# 1_P1.net
KiCad netlist of a schematic drawn in Altium Designer
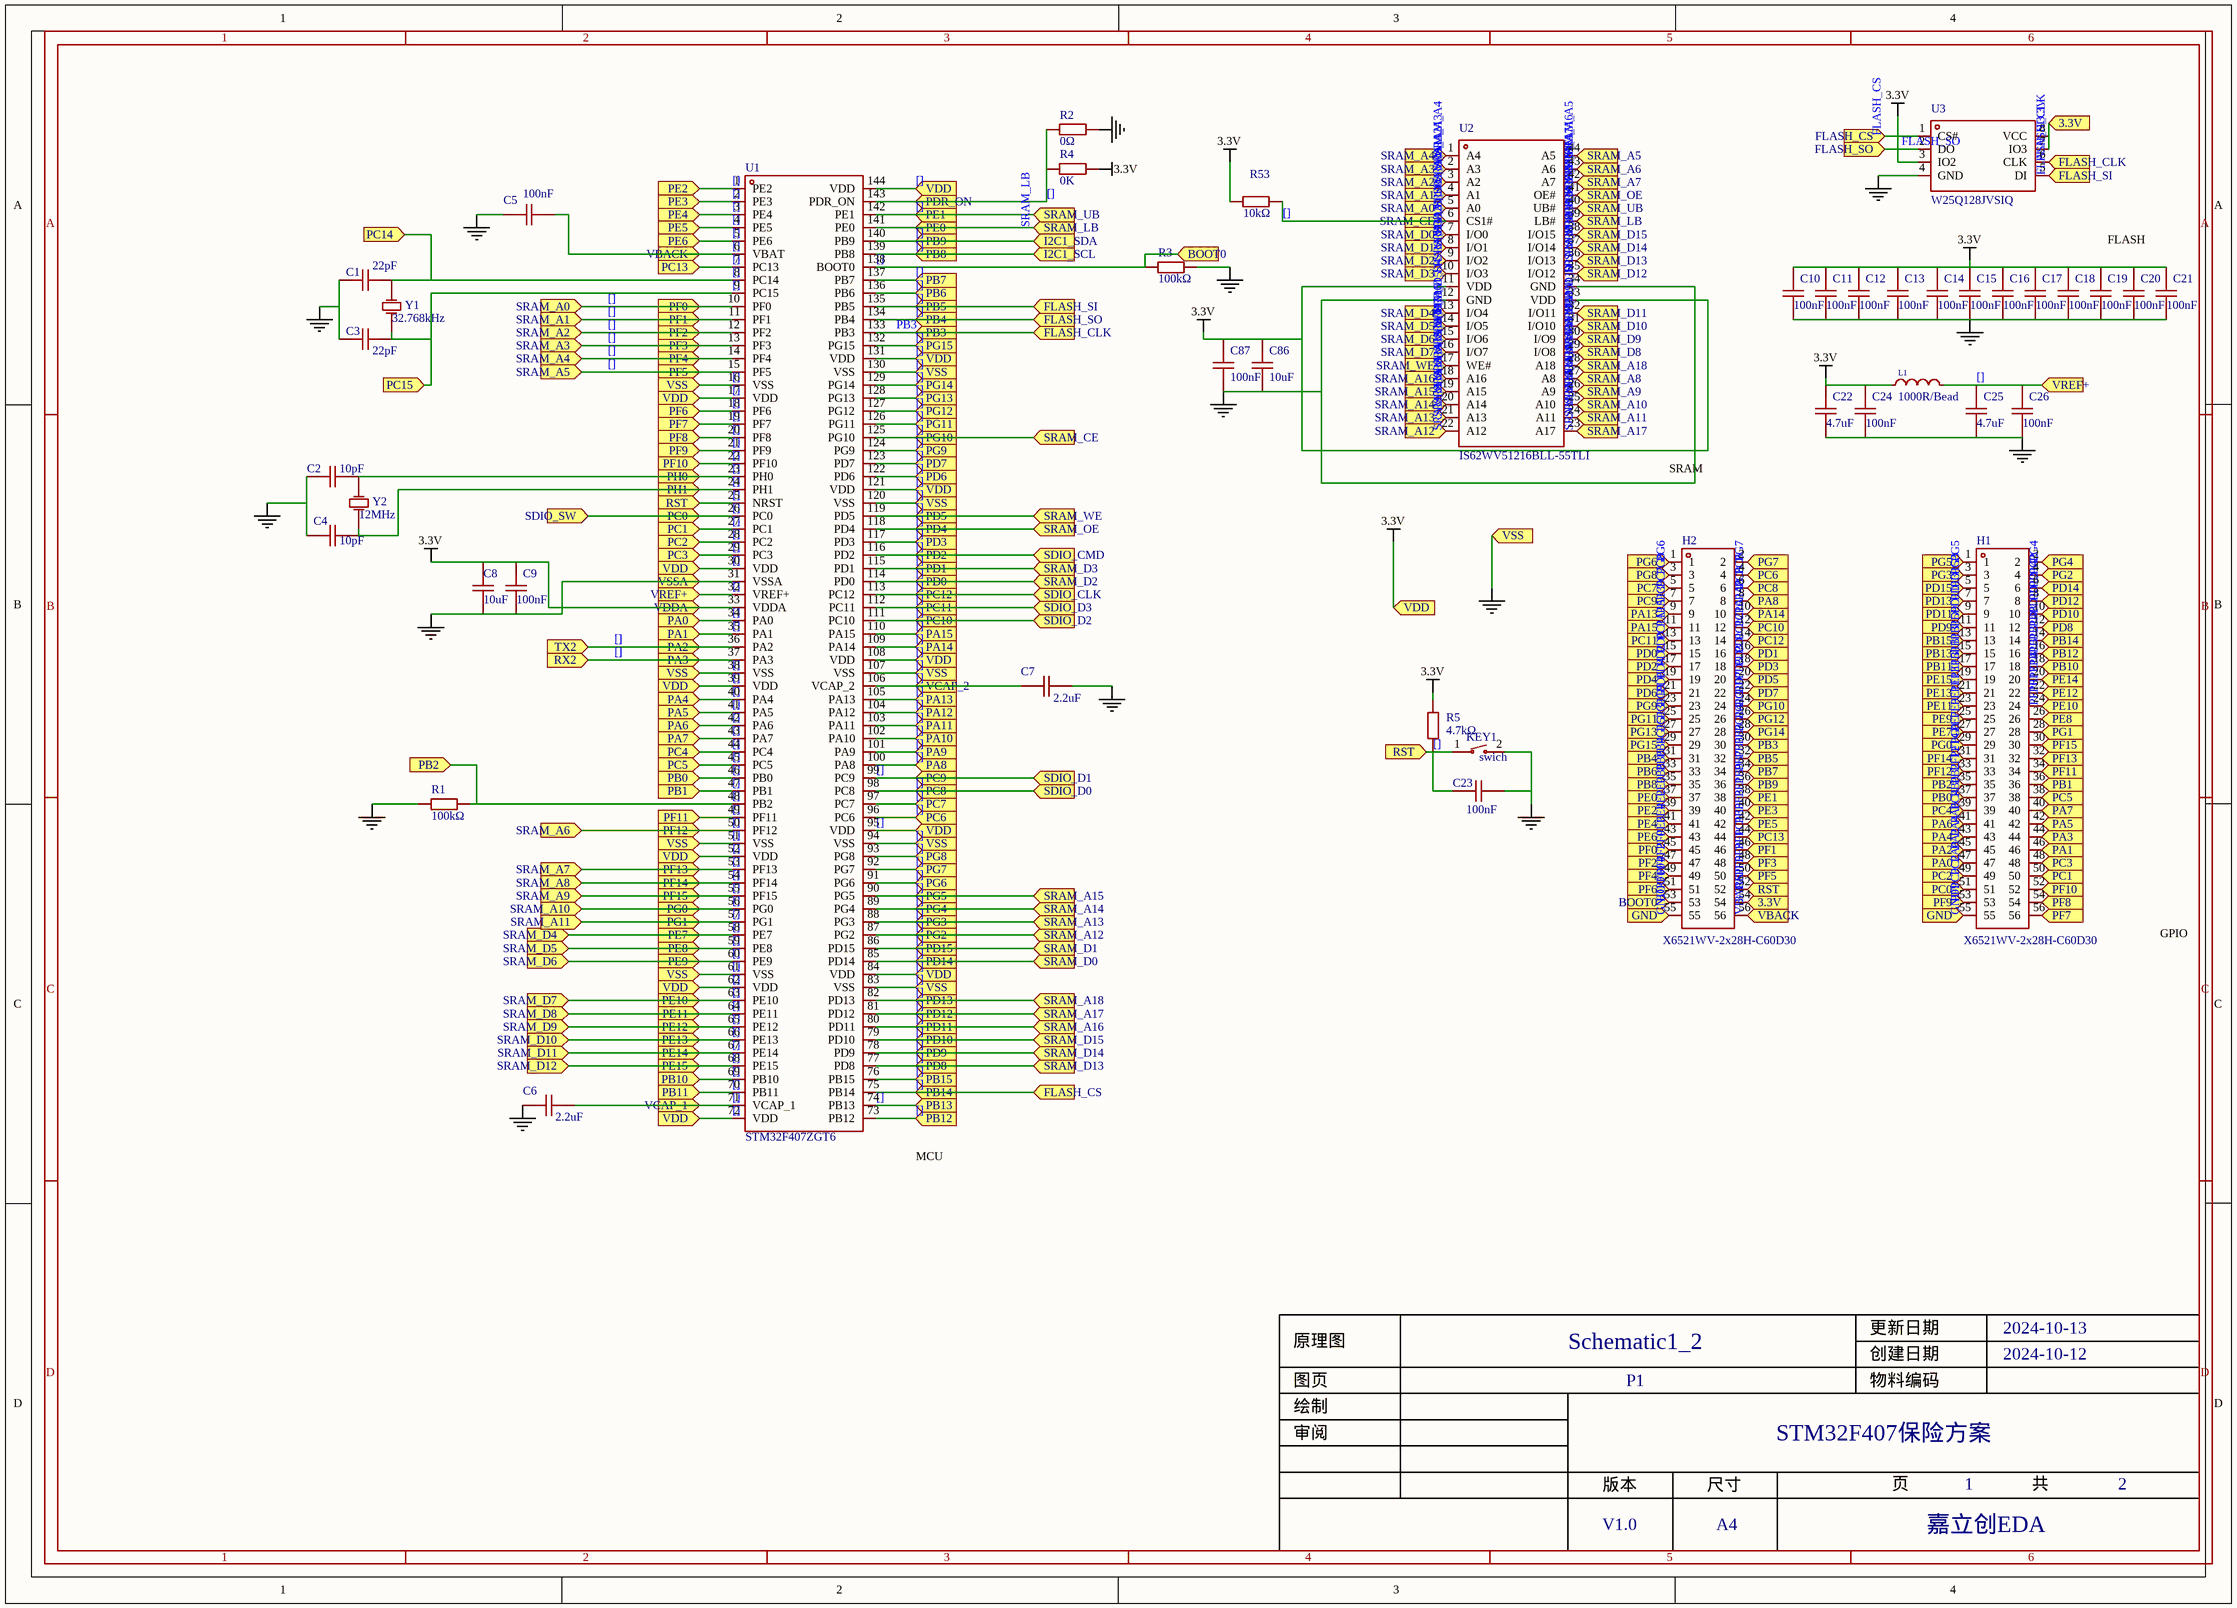
[diagram p0: 1_P1.schdoc]

(export (version "E")
  (design (tool "Eeschema 10.0.6"))
  (components
    (comp (ref "C1")
      (value "22pF")
      (footprint "C0805")
      (description "容值:22pF;精度:±5%;额定电压:50V;材质(温度系数):NP0;")
      (fields
        (field (name "MANUFACTURER") "YAGEO(国巨)")
        (field (name "MANUFACTURER PART") "CC0805JRNPO9BN220")
      )
      (libsource (lib "altium-import") (part "root_0_CC0805JRNPO9BN220_"))
    )
    (comp (ref "C2")
      (value "10pF")
      (footprint "C0805")
      (description "容值:10pF;精度:±5%;额定电压:50V;材质(温度系数):NP0;")
      (fields
        (field (name "MANUFACTURER") "YAGEO(国巨)")
        (field (name "MANUFACTURER PART") "CC0805JRNPO9BN100")
      )
      (libsource (lib "altium-import") (part "root_0_CC0805JRNPO9BN100_"))
    )
    (comp (ref "C3")
      (value "22pF")
      (footprint "C0805")
      (description "容值:22pF;精度:±5%;额定电压:50V;材质(温度系数):NP0;")
      (fields
        (field (name "MANUFACTURER") "YAGEO(国巨)")
        (field (name "MANUFACTURER PART") "CC0805JRNPO9BN220")
      )
      (libsource (lib "altium-import") (part "root_0_CC0805JRNPO9BN220_"))
    )
    (comp (ref "C4")
      (value "10pF")
      (footprint "C0805")
      (description "容值:10pF;精度:±5%;额定电压:50V;材质(温度系数):NP0;")
      (fields
        (field (name "MANUFACTURER") "YAGEO(国巨)")
        (field (name "MANUFACTURER PART") "CC0805JRNPO9BN100")
      )
      (libsource (lib "altium-import") (part "root_0_CC0805JRNPO9BN100_"))
    )
    (comp (ref "C5")
      (value "100nF")
      (footprint "C0805")
      (description "容值:100nF;精度:±10%;额定电压:50V;材质(温度系数):X7R;")
      (fields
        (field (name "MANUFACTURER") "YAGEO(国巨)")
        (field (name "MANUFACTURER PART") "CC0805KRX7R9BB104")
      )
      (libsource (lib "altium-import") (part "root_2_CC0805KRX7R9BB104_"))
    )
    (comp (ref "C6")
      (value "2.2uF")
      (footprint "C0805")
      (description "容值:2.2uF;精度:±10%;额定电压:50V;材质(温度系数):X7R;")
      (fields
        (field (name "MANUFACTURER") "YAGEO(国巨)")
        (field (name "MANUFACTURER PART") "CC0805KKX7R9BB225")
      )
      (libsource (lib "altium-import") (part "root_2_CC0805KKX7R9BB225_"))
    )
    (comp (ref "C7")
      (value "2.2uF")
      (footprint "C0805")
      (description "容值:2.2uF;精度:±10%;额定电压:50V;材质(温度系数):X7R;")
      (fields
        (field (name "MANUFACTURER") "YAGEO(国巨)")
        (field (name "MANUFACTURER PART") "CC0805KKX7R9BB225")
      )
      (libsource (lib "altium-import") (part "root_2_CC0805KKX7R9BB225_"))
    )
    (comp (ref "C8")
      (value "10uF")
      (footprint "C0805")
      (description "容值:10uF;精度:±10%;额定电压:25V;材质(温度系数):X5R;")
      (fields
        (field (name "MANUFACTURER") "YAGEO(国巨)")
        (field (name "MANUFACTURER PART") "CC0805KKX5R8BB106")
      )
      (libsource (lib "altium-import") (part "root_3_CC0805KKX5R8BB106_C89831_"))
    )
    (comp (ref "C9")
      (value "100nF")
      (footprint "C0805")
      (description "容值:100nF;精度:±10%;额定电压:50V;材质(温度系数):X7R;")
      (fields
        (field (name "MANUFACTURER") "YAGEO(国巨)")
        (field (name "MANUFACTURER PART") "CC0805KRX7R9BB104")
      )
      (libsource (lib "altium-import") (part "root_3_CC0805KRX7R9BB104_"))
    )
    (comp (ref "C10")
      (value "100nF")
      (footprint "C0805")
      (description "容值:100nF;精度:±10%;额定电压:50V;材质(温度系数):X7R;")
      (fields
        (field (name "MANUFACTURER") "YAGEO(国巨)")
        (field (name "MANUFACTURER PART") "CC0805KRX7R9BB104")
      )
      (libsource (lib "altium-import") (part "root_1_CC0805KRX7R9BB104_"))
    )
    (comp (ref "C11")
      (value "100nF")
      (footprint "C0805")
      (description "容值:100nF;精度:±10%;额定电压:50V;材质(温度系数):X7R;")
      (fields
        (field (name "MANUFACTURER") "YAGEO(国巨)")
        (field (name "MANUFACTURER PART") "CC0805KRX7R9BB104")
      )
      (libsource (lib "altium-import") (part "root_1_CC0805KRX7R9BB104_"))
    )
    (comp (ref "C12")
      (value "100nF")
      (footprint "C0805")
      (description "容值:100nF;精度:±10%;额定电压:50V;材质(温度系数):X7R;")
      (fields
        (field (name "MANUFACTURER") "YAGEO(国巨)")
        (field (name "MANUFACTURER PART") "CC0805KRX7R9BB104")
      )
      (libsource (lib "altium-import") (part "root_1_CC0805KRX7R9BB104_"))
    )
    (comp (ref "C13")
      (value "100nF")
      (footprint "C0805")
      (description "容值:100nF;精度:±10%;额定电压:50V;材质(温度系数):X7R;")
      (fields
        (field (name "MANUFACTURER") "YAGEO(国巨)")
        (field (name "MANUFACTURER PART") "CC0805KRX7R9BB104")
      )
      (libsource (lib "altium-import") (part "root_1_CC0805KRX7R9BB104_"))
    )
    (comp (ref "C14")
      (value "100nF")
      (footprint "C0805")
      (description "容值:100nF;精度:±10%;额定电压:50V;材质(温度系数):X7R;")
      (fields
        (field (name "MANUFACTURER") "YAGEO(国巨)")
        (field (name "MANUFACTURER PART") "CC0805KRX7R9BB104")
      )
      (libsource (lib "altium-import") (part "root_1_CC0805KRX7R9BB104_"))
    )
    (comp (ref "C15")
      (value "100nF")
      (footprint "C0805")
      (description "容值:100nF;精度:±10%;额定电压:50V;材质(温度系数):X7R;")
      (fields
        (field (name "MANUFACTURER") "YAGEO(国巨)")
        (field (name "MANUFACTURER PART") "CC0805KRX7R9BB104")
      )
      (libsource (lib "altium-import") (part "root_1_CC0805KRX7R9BB104_"))
    )
    (comp (ref "C16")
      (value "100nF")
      (footprint "C0805")
      (description "容值:100nF;精度:±10%;额定电压:50V;材质(温度系数):X7R;")
      (fields
        (field (name "MANUFACTURER") "YAGEO(国巨)")
        (field (name "MANUFACTURER PART") "CC0805KRX7R9BB104")
      )
      (libsource (lib "altium-import") (part "root_1_CC0805KRX7R9BB104_"))
    )
    (comp (ref "C17")
      (value "100nF")
      (footprint "C0805")
      (description "容值:100nF;精度:±10%;额定电压:50V;材质(温度系数):X7R;")
      (fields
        (field (name "MANUFACTURER") "YAGEO(国巨)")
        (field (name "MANUFACTURER PART") "CC0805KRX7R9BB104")
      )
      (libsource (lib "altium-import") (part "root_1_CC0805KRX7R9BB104_"))
    )
    (comp (ref "C18")
      (value "100nF")
      (footprint "C0805")
      (description "容值:100nF;精度:±10%;额定电压:50V;材质(温度系数):X7R;")
      (fields
        (field (name "MANUFACTURER") "YAGEO(国巨)")
        (field (name "MANUFACTURER PART") "CC0805KRX7R9BB104")
      )
      (libsource (lib "altium-import") (part "root_1_CC0805KRX7R9BB104_"))
    )
    (comp (ref "C19")
      (value "100nF")
      (footprint "C0805")
      (description "容值:100nF;精度:±10%;额定电压:50V;材质(温度系数):X7R;")
      (fields
        (field (name "MANUFACTURER") "YAGEO(国巨)")
        (field (name "MANUFACTURER PART") "CC0805KRX7R9BB104")
      )
      (libsource (lib "altium-import") (part "root_1_CC0805KRX7R9BB104_"))
    )
    (comp (ref "C20")
      (value "100nF")
      (footprint "C0805")
      (description "容值:100nF;精度:±10%;额定电压:50V;材质(温度系数):X7R;")
      (fields
        (field (name "MANUFACTURER") "YAGEO(国巨)")
        (field (name "MANUFACTURER PART") "CC0805KRX7R9BB104")
      )
      (libsource (lib "altium-import") (part "root_1_CC0805KRX7R9BB104_"))
    )
    (comp (ref "C21")
      (value "100nF")
      (footprint "C0805")
      (description "容值:100nF;精度:±10%;额定电压:50V;材质(温度系数):X7R;")
      (fields
        (field (name "MANUFACTURER") "YAGEO(国巨)")
        (field (name "MANUFACTURER PART") "CC0805KRX7R9BB104")
      )
      (libsource (lib "altium-import") (part "root_1_CC0805KRX7R9BB104_"))
    )
    (comp (ref "C22")
      (value "4.7uF")
      (footprint "C0805")
      (description "容值:4.7uF;精度:±10%;额定电压:25V;材质(温度系数):X5R;")
      (fields
        (field (name "MANUFACTURER") "SAMSUNG(三星)")
        (field (name "MANUFACTURER PART") "CL21A475KAQNNNE")
      )
      (libsource (lib "altium-import") (part "root_1_CL21A475KAQNNNE_"))
    )
    (comp (ref "C23")
      (value "100nF")
      (footprint "C0805")
      (description "容值:100nF;精度:±10%;额定电压:50V;材质(温度系数):X7R;")
      (fields
        (field (name "MANUFACTURER") "YAGEO(国巨)")
        (field (name "MANUFACTURER PART") "CC0805KRX7R9BB104")
      )
      (libsource (lib "altium-import") (part "root_2_CC0805KRX7R9BB104_"))
    )
    (comp (ref "C24")
      (value "100nF")
      (footprint "C0805")
      (description "容值:100nF;精度:±10%;额定电压:50V;材质(温度系数):X7R;")
      (fields
        (field (name "MANUFACTURER") "YAGEO(国巨)")
        (field (name "MANUFACTURER PART") "CC0805KRX7R9BB104")
      )
      (libsource (lib "altium-import") (part "root_1_CC0805KRX7R9BB104_"))
    )
    (comp (ref "C25")
      (value "4.7uF")
      (footprint "C0805")
      (description "容值:4.7uF;精度:±10%;额定电压:25V;材质(温度系数):X5R;")
      (fields
        (field (name "MANUFACTURER") "SAMSUNG(三星)")
        (field (name "MANUFACTURER PART") "CL21A475KAQNNNE")
      )
      (libsource (lib "altium-import") (part "root_1_CL21A475KAQNNNE_"))
    )
    (comp (ref "C26")
      (value "100nF")
      (footprint "C0805")
      (description "容值:100nF;精度:±10%;额定电压:50V;材质(温度系数):X7R;")
      (fields
        (field (name "MANUFACTURER") "YAGEO(国巨)")
        (field (name "MANUFACTURER PART") "CC0805KRX7R9BB104")
      )
      (libsource (lib "altium-import") (part "root_1_CC0805KRX7R9BB104_"))
    )
    (comp (ref "C86")
      (value "10uF")
      (footprint "C0805")
      (description "容值:10uF;精度:±10%;额定电压:25V;材质(温度系数):X5R;")
      (fields
        (field (name "MANUFACTURER") "SAMSUNG(三星)")
        (field (name "MANUFACTURER PART") "CL21A106KAYNNNE")
      )
      (libsource (lib "altium-import") (part "root_3_CL21A106KAYNNNE_C15850_"))
    )
    (comp (ref "C87")
      (value "100nF")
      (footprint "C0805")
      (description "容值:100nF;精度:±10%;额定电压:50V;材质(温度系数):X7R;")
      (fields
        (field (name "MANUFACTURER") "YAGEO(国巨)")
        (field (name "MANUFACTURER PART") "CC0805KRX7R9BB104")
      )
      (libsource (lib "altium-import") (part "root_3_CC0805KRX7R9BB104_"))
    )
    (comp (ref "H1")
      (value "X6521WV-2x28H-C60D30")
      (footprint "HDR-TH_56P-2.54-V-M-R2-C28-S2.54")
      (fields (field (name "MANUFACTURER") "XKB Connection(中国星坤)"))
      (libsource (lib "altium-import") (part "root_0_X6521WV-2x28H-C60D30_"))
    )
    (comp (ref "H2")
      (value "X6521WV-2x28H-C60D30")
      (footprint "HDR-TH_56P-2.54-V-M-R2-C28-S2.54")
      (fields (field (name "MANUFACTURER") "XKB Connection(中国星坤)"))
      (libsource (lib "altium-import") (part "root_0_X6521WV-2x28H-C60D30_"))
    )
    (comp (ref "KEY1")
      (value "swich")
      (footprint "KEY-SMD_L6.0-W3.6-LS8.0")
      (fields (field (name "MANUFACTURER") "USAKRO(美韩)"))
      (libsource (lib "altium-import") (part "root_0_UK-B0240-R-250-JZ_"))
    )
    (comp (ref "L1")
      (value "1000R/Bead")
      (footprint "L0805")
      (description "标称阻抗@测试频率:1kΩ@100MHz;直流电阻(RDC):120mΩ;")
      (fields (field (name "MANUFACTURER") "chilisin(奇力新)"))
      (libsource (lib "altium-import") (part "root_0_ABPY00201209102Y00_C2847077_"))
    )
    (comp (ref "R1")
      (value "100kΩ")
      (footprint "R0805")
      (description "电阻类型:厚膜电阻;阻值:100kΩ;精度:±1%;功率:125mW;最大工作电压:150V;温度系数:±100ppm/℃;")
      (fields
        (field (name "MANUFACTURER") "UNI-ROYAL(厚声)")
        (field (name "MANUFACTURER PART") "0805W8F1003T5E")
      )
      (libsource (lib "altium-import") (part "root_2_0805W8F1003T5E_"))
    )
    (comp (ref "R2")
      (value "0Ω")
      (footprint "R0805")
      (description "电阻类型:厚膜电阻;阻值:0Ω;精度:±1%;功率:125mW;最大工作电压:150V;温度系数:±800ppm/℃;")
      (fields
        (field (name "MANUFACTURER") "UNI-ROYAL(厚声)")
        (field (name "MANUFACTURER PART") "0805W8F0000T5E")
      )
      (libsource (lib "altium-import") (part "root_0_0805W8F0000T5E_"))
    )
    (comp (ref "R3")
      (value "100kΩ")
      (footprint "R0805")
      (description "电阻类型:厚膜电阻;阻值:100kΩ;精度:±1%;功率:125mW;最大工作电压:150V;温度系数:±100ppm/℃;")
      (fields
        (field (name "MANUFACTURER") "UNI-ROYAL(厚声)")
        (field (name "MANUFACTURER PART") "0805W8F1003T5E")
      )
      (libsource (lib "altium-import") (part "root_0_0805W8F1003T5E_"))
    )
    (comp (ref "R4")
      (value "0K")
      (footprint "R0805")
      (libsource (lib "altium-import") (part "root_0_Res_0603_"))
    )
    (comp (ref "R5")
      (value "4.7kΩ")
      (footprint "R0805")
      (description "电阻类型:厚膜电阻;阻值:4.7kΩ;精度:±1%;功率:125mW;最大工作电压:150V;温度系数:±100ppm/℃;")
      (fields
        (field (name "MANUFACTURER") "UNI-ROYAL(厚声)")
        (field (name "MANUFACTURER PART") "0805W8F4701T5E")
      )
      (libsource (lib "altium-import") (part "root_1_0805W8F4701T5E_"))
    )
    (comp (ref "R53")
      (value "10kΩ")
      (footprint "R0805")
      (description "电阻类型:厚膜电阻;阻值:10kΩ;精度:±1%;功率:125mW;最大工作电压:150V;温度系数:±100ppm/℃;")
      (fields
        (field (name "MANUFACTURER") "UNI-ROYAL(厚声)")
        (field (name "MANUFACTURER PART") "0805W8F1002T5E")
      )
      (libsource (lib "altium-import") (part "root_2_0805W8F1002T5E_C17414_"))
    )
    (comp (ref "U1")
      (value "STM32F407ZGT6")
      (footprint "LQFP-144_L20.0-W20.0-P0.50-LS22.0-BL")
      (description "CPU内核:ARM-M4;程序存储容量:1MB;RAM总容量:192KB;GPIO端口数量:114;工作电压范围:1.8V~3.6V;CPU最大主频:168MHz;程序存储器类型:FLASH;")
      (fields (field (name "MANUFACTURER") "ST(意法半导体)"))
      (libsource (lib "altium-import") (part "root_0_STM32F407ZGT6_"))
    )
    (comp (ref "U2")
      (value "IS62WV51216BLL-55TLI")
      (footprint "TSOP-44_L18.4-W10.2-P0.80-LS11.8-BL")
      (description "8-Mbit(512K × 16bit)，并行接口，工作电压：2.5V to 3.6V")
      (fields (field (name "MANUFACTURER") "ISSI(美国芯成)"))
      (libsource (lib "altium-import") (part "root_0_IS62WV51216BLL-55TLI_"))
    )
    (comp (ref "U3")
      (value "W25Q128JVSIQ")
      (footprint "SOIC-8_L5.3-W5.3-P1.27-LS8.0-BL")
      (description "接口类型:SPI;存储容量:128Mbit;")
      (fields (field (name "MANUFACTURER") "WINBOND(华邦)"))
      (libsource (lib "altium-import") (part "root_0_W25Q128JVSIQ_C113767_"))
    )
    (comp (ref "Y1")
      (value "32.768kHz")
      (footprint "OSC-TH_BD3.1-P0.8-D0.3")
      (description "晶振类型:直插晶振;频率:32.768kHz;常温频差:±10ppm;外接负载电容:12.5pF;频率稳定度(全温):-;")
      (fields (field (name "MANUFACTURER") "YXC(扬兴晶振)") (field (name "MANUFACTURER PART") "X308032768KGB2SC"))
      (libsource (lib "altium-import") (part "root_1_X308032768KGB2SC_"))
    )
    (comp (ref "Y2")
      (value "12MHz")
      (footprint "HC-49US_L11.5-W4.5-P4.88")
      (description "晶振类型:直插晶振;频率:12MHz;常温频差:±30ppm;外接负载电容:20pF;频率稳定度(全温):±30ppm;")
      (fields (field (name "MANUFACTURER") "YJX(雅晶鑫)") (field (name "MANUFACTURER PART") "TAXD12M2GLFBET2T"))
      (libsource (lib "altium-import") (part "root_1_TAXD12M2GLFBET2T_"))
    )
  )
  (nets
    (net (code "1") (name "/FLASH_CLK") (class "Default")
      (node (ref "H2") (pin "30") (pinfunction "30_30") (pintype "passive"))
      (node (ref "U1") (pin "133") (pinfunction "PB3_133") (pintype "passive"))
      (node (ref "U3") (pin "6") (pinfunction "CLK_6") (pintype "passive"))
    )
    (net (code "2") (name "/PE0") (class "Default")
      (node (ref "H2") (pin "37") (pinfunction "37_37") (pintype "passive"))
      (node (ref "U1") (pin "141") (pinfunction "PE0_141") (pintype "passive"))
      (node (ref "U2") (pin "39") (pinfunction "LB#_39") (pintype "passive"))
    )
    (net (code "3") (name "3.3V") (class "Default")
      (node (ref "C1") (pin "2") (pinfunction "2_2") (pintype "passive"))
      (node (ref "C10") (pin "2") (pinfunction "2_2") (pintype "passive"))
      (node (ref "C11") (pin "2") (pinfunction "2_2") (pintype "passive"))
      (node (ref "C12") (pin "2") (pinfunction "2_2") (pintype "passive"))
      (node (ref "C13") (pin "2") (pinfunction "2_2") (pintype "passive"))
      (node (ref "C14") (pin "2") (pinfunction "2_2") (pintype "passive"))
      (node (ref "C15") (pin "2") (pinfunction "2_2") (pintype "passive"))
      (node (ref "C16") (pin "2") (pinfunction "2_2") (pintype "passive"))
      (node (ref "C17") (pin "2") (pinfunction "2_2") (pintype "passive"))
      (node (ref "C18") (pin "2") (pinfunction "2_2") (pintype "passive"))
      (node (ref "C19") (pin "2") (pinfunction "2_2") (pintype "passive"))
      (node (ref "C2") (pin "2") (pinfunction "2_2") (pintype "passive"))
      (node (ref "C20") (pin "2") (pinfunction "2_2") (pintype "passive"))
      (node (ref "C21") (pin "2") (pinfunction "2_2") (pintype "passive"))
      (node (ref "C22") (pin "2") (pinfunction "2_2") (pintype "passive"))
      (node (ref "C23") (pin "2") (pinfunction "2_2") (pintype "passive"))
      (node (ref "C24") (pin "2") (pinfunction "2_2") (pintype "passive"))
      (node (ref "C25") (pin "2") (pinfunction "2_2") (pintype "passive"))
      (node (ref "C26") (pin "2") (pinfunction "2_2") (pintype "passive"))
      (node (ref "C3") (pin "2") (pinfunction "2_2") (pintype "passive"))
      (node (ref "C4") (pin "2") (pinfunction "2_2") (pintype "passive"))
      (node (ref "C5") (pin "1") (pinfunction "1_1") (pintype "passive"))
      (node (ref "C6") (pin "1") (pinfunction "1_1") (pintype "passive"))
      (node (ref "C7") (pin "2") (pinfunction "2_2") (pintype "passive"))
      (node (ref "C8") (pin "1") (pinfunction "1_1") (pintype "passive"))
      (node (ref "C86") (pin "1") (pinfunction "1_1") (pintype "passive"))
      (node (ref "C87") (pin "1") (pinfunction "1_1") (pintype "passive"))
      (node (ref "C9") (pin "1") (pinfunction "1_1") (pintype "passive"))
      (node (ref "H1") (pin "1") (pinfunction "1_1") (pintype "passive"))
      (node (ref "H1") (pin "10") (pinfunction "10_10") (pintype "passive"))
      (node (ref "H1") (pin "11") (pinfunction "11_11") (pintype "passive"))
      (node (ref "H1") (pin "12") (pinfunction "12_12") (pintype "passive"))
      (node (ref "H1") (pin "13") (pinfunction "13_13") (pintype "passive"))
      (node (ref "H1") (pin "14") (pinfunction "14_14") (pintype "passive"))
      (node (ref "H1") (pin "15") (pinfunction "15_15") (pintype "passive"))
      (node (ref "H1") (pin "16") (pinfunction "16_16") (pintype "passive"))
      (node (ref "H1") (pin "17") (pinfunction "17_17") (pintype "passive"))
      (node (ref "H1") (pin "18") (pinfunction "18_18") (pintype "passive"))
      (node (ref "H1") (pin "19") (pinfunction "19_19") (pintype "passive"))
      (node (ref "H1") (pin "2") (pinfunction "2_2") (pintype "passive"))
      (node (ref "H1") (pin "20") (pinfunction "20_20") (pintype "passive"))
      (node (ref "H1") (pin "21") (pinfunction "21_21") (pintype "passive"))
      (node (ref "H1") (pin "22") (pinfunction "22_22") (pintype "passive"))
      (node (ref "H1") (pin "23") (pinfunction "23_23") (pintype "passive"))
      (node (ref "H1") (pin "24") (pinfunction "24_24") (pintype "passive"))
      (node (ref "H1") (pin "25") (pinfunction "25_25") (pintype "passive"))
      (node (ref "H1") (pin "26") (pinfunction "26_26") (pintype "passive"))
      (node (ref "H1") (pin "27") (pinfunction "27_27") (pintype "passive"))
      (node (ref "H1") (pin "28") (pinfunction "28_28") (pintype "passive"))
      (node (ref "H1") (pin "29") (pinfunction "29_29") (pintype "passive"))
      (node (ref "H1") (pin "3") (pinfunction "3_3") (pintype "passive"))
      (node (ref "H1") (pin "30") (pinfunction "30_30") (pintype "passive"))
      (node (ref "H1") (pin "31") (pinfunction "31_31") (pintype "passive"))
      (node (ref "H1") (pin "32") (pinfunction "32_32") (pintype "passive"))
      (node (ref "H1") (pin "33") (pinfunction "33_33") (pintype "passive"))
      (node (ref "H1") (pin "34") (pinfunction "34_34") (pintype "passive"))
      (node (ref "H1") (pin "35") (pinfunction "35_35") (pintype "passive"))
      (node (ref "H1") (pin "36") (pinfunction "36_36") (pintype "passive"))
      (node (ref "H1") (pin "37") (pinfunction "37_37") (pintype "passive"))
      (node (ref "H1") (pin "38") (pinfunction "38_38") (pintype "passive"))
      (node (ref "H1") (pin "39") (pinfunction "39_39") (pintype "passive"))
      (node (ref "H1") (pin "4") (pinfunction "4_4") (pintype "passive"))
      (node (ref "H1") (pin "40") (pinfunction "40_40") (pintype "passive"))
      (node (ref "H1") (pin "41") (pinfunction "41_41") (pintype "passive"))
      (node (ref "H1") (pin "42") (pinfunction "42_42") (pintype "passive"))
      (node (ref "H1") (pin "43") (pinfunction "43_43") (pintype "passive"))
      (node (ref "H1") (pin "44") (pinfunction "44_44") (pintype "passive"))
      (node (ref "H1") (pin "45") (pinfunction "45_45") (pintype "passive"))
      (node (ref "H1") (pin "46") (pinfunction "46_46") (pintype "passive"))
      (node (ref "H1") (pin "47") (pinfunction "47_47") (pintype "passive"))
      (node (ref "H1") (pin "48") (pinfunction "48_48") (pintype "passive"))
      (node (ref "H1") (pin "49") (pinfunction "49_49") (pintype "passive"))
      (node (ref "H1") (pin "5") (pinfunction "5_5") (pintype "passive"))
      (node (ref "H1") (pin "50") (pinfunction "50_50") (pintype "passive"))
      (node (ref "H1") (pin "51") (pinfunction "51_51") (pintype "passive"))
      (node (ref "H1") (pin "52") (pinfunction "52_52") (pintype "passive"))
      (node (ref "H1") (pin "53") (pinfunction "53_53") (pintype "passive"))
      (node (ref "H1") (pin "54") (pinfunction "54_54") (pintype "passive"))
      (node (ref "H1") (pin "56") (pinfunction "56_56") (pintype "passive"))
      (node (ref "H1") (pin "6") (pinfunction "6_6") (pintype "passive"))
      (node (ref "H1") (pin "7") (pinfunction "7_7") (pintype "passive"))
      (node (ref "H1") (pin "8") (pinfunction "8_8") (pintype "passive"))
      (node (ref "H1") (pin "9") (pinfunction "9_9") (pintype "passive"))
      (node (ref "H2") (pin "1") (pinfunction "1_1") (pintype "passive"))
      (node (ref "H2") (pin "10") (pinfunction "10_10") (pintype "passive"))
      (node (ref "H2") (pin "11") (pinfunction "11_11") (pintype "passive"))
      (node (ref "H2") (pin "12") (pinfunction "12_12") (pintype "passive"))
      (node (ref "H2") (pin "13") (pinfunction "13_13") (pintype "passive"))
      (node (ref "H2") (pin "14") (pinfunction "14_14") (pintype "passive"))
      (node (ref "H2") (pin "15") (pinfunction "15_15") (pintype "passive"))
      (node (ref "H2") (pin "16") (pinfunction "16_16") (pintype "passive"))
      (node (ref "H2") (pin "17") (pinfunction "17_17") (pintype "passive"))
      (node (ref "H2") (pin "18") (pinfunction "18_18") (pintype "passive"))
      (node (ref "H2") (pin "19") (pinfunction "19_19") (pintype "passive"))
      (node (ref "H2") (pin "2") (pinfunction "2_2") (pintype "passive"))
      (node (ref "H2") (pin "20") (pinfunction "20_20") (pintype "passive"))
      (node (ref "H2") (pin "21") (pinfunction "21_21") (pintype "passive"))
      (node (ref "H2") (pin "22") (pinfunction "22_22") (pintype "passive"))
      (node (ref "H2") (pin "23") (pinfunction "23_23") (pintype "passive"))
      (node (ref "H2") (pin "24") (pinfunction "24_24") (pintype "passive"))
      (node (ref "H2") (pin "25") (pinfunction "25_25") (pintype "passive"))
      (node (ref "H2") (pin "26") (pinfunction "26_26") (pintype "passive"))
      (node (ref "H2") (pin "27") (pinfunction "27_27") (pintype "passive"))
      (node (ref "H2") (pin "28") (pinfunction "28_28") (pintype "passive"))
      (node (ref "H2") (pin "29") (pinfunction "29_29") (pintype "passive"))
      (node (ref "H2") (pin "3") (pinfunction "3_3") (pintype "passive"))
      (node (ref "H2") (pin "31") (pinfunction "31_31") (pintype "passive"))
      (node (ref "H2") (pin "32") (pinfunction "32_32") (pintype "passive"))
      (node (ref "H2") (pin "33") (pinfunction "33_33") (pintype "passive"))
      (node (ref "H2") (pin "34") (pinfunction "34_34") (pintype "passive"))
      (node (ref "H2") (pin "35") (pinfunction "35_35") (pintype "passive"))
      (node (ref "H2") (pin "36") (pinfunction "36_36") (pintype "passive"))
      (node (ref "H2") (pin "38") (pinfunction "38_38") (pintype "passive"))
      (node (ref "H2") (pin "39") (pinfunction "39_39") (pintype "passive"))
      (node (ref "H2") (pin "4") (pinfunction "4_4") (pintype "passive"))
      (node (ref "H2") (pin "40") (pinfunction "40_40") (pintype "passive"))
      (node (ref "H2") (pin "41") (pinfunction "41_41") (pintype "passive"))
      (node (ref "H2") (pin "42") (pinfunction "42_42") (pintype "passive"))
      (node (ref "H2") (pin "43") (pinfunction "43_43") (pintype "passive"))
      (node (ref "H2") (pin "44") (pinfunction "44_44") (pintype "passive"))
      (node (ref "H2") (pin "45") (pinfunction "45_45") (pintype "passive"))
      (node (ref "H2") (pin "46") (pinfunction "46_46") (pintype "passive"))
      (node (ref "H2") (pin "47") (pinfunction "47_47") (pintype "passive"))
      (node (ref "H2") (pin "48") (pinfunction "48_48") (pintype "passive"))
      (node (ref "H2") (pin "49") (pinfunction "49_49") (pintype "passive"))
      (node (ref "H2") (pin "5") (pinfunction "5_5") (pintype "passive"))
      (node (ref "H2") (pin "50") (pinfunction "50_50") (pintype "passive"))
      (node (ref "H2") (pin "51") (pinfunction "51_51") (pintype "passive"))
      (node (ref "H2") (pin "52") (pinfunction "52_52") (pintype "passive"))
      (node (ref "H2") (pin "53") (pinfunction "53_53") (pintype "passive"))
      (node (ref "H2") (pin "54") (pinfunction "54_54") (pintype "passive"))
      (node (ref "H2") (pin "56") (pinfunction "56_56") (pintype "passive"))
      (node (ref "H2") (pin "6") (pinfunction "6_6") (pintype "passive"))
      (node (ref "H2") (pin "7") (pinfunction "7_7") (pintype "passive"))
      (node (ref "H2") (pin "8") (pinfunction "8_8") (pintype "passive"))
      (node (ref "H2") (pin "9") (pinfunction "9_9") (pintype "passive"))
      (node (ref "KEY1") (pin "1") (pinfunction "1_1") (pintype "passive"))
      (node (ref "L1") (pin "1") (pinfunction "1_1") (pintype "passive"))
      (node (ref "L1") (pin "2") (pinfunction "2_2") (pintype "passive"))
      (node (ref "R1") (pin "1") (pinfunction "1_1") (pintype "passive"))
      (node (ref "R2") (pin "1") (pinfunction "1_1") (pintype "passive"))
      (node (ref "R3") (pin "1") (pinfunction "1_1") (pintype "passive"))
      (node (ref "R4") (pin "1") (pinfunction "1_1") (pintype "passive"))
      (node (ref "R4") (pin "2") (pinfunction "2_2") (pintype "passive"))
      (node (ref "R5") (pin "1") (pinfunction "1_1") (pintype "passive"))
      (node (ref "R5") (pin "2") (pinfunction "2_2") (pintype "passive"))
      (node (ref "R53") (pin "1") (pinfunction "1_1") (pintype "passive"))
      (node (ref "R53") (pin "2") (pinfunction "2_2") (pintype "passive"))
      (node (ref "U1") (pin "1") (pinfunction "PE2_1") (pintype "passive"))
      (node (ref "U1") (pin "10") (pinfunction "PF0_10") (pintype "passive"))
      (node (ref "U1") (pin "100") (pinfunction "PA8_100") (pintype "passive"))
      (node (ref "U1") (pin "101") (pinfunction "PA9_101") (pintype "passive"))
      (node (ref "U1") (pin "102") (pinfunction "PA10_102") (pintype "passive"))
      (node (ref "U1") (pin "103") (pinfunction "PA11_103") (pintype "passive"))
      (node (ref "U1") (pin "104") (pinfunction "PA12_104") (pintype "passive"))
      (node (ref "U1") (pin "105") (pinfunction "PA13_105") (pintype "passive"))
      (node (ref "U1") (pin "106") (pinfunction "VCAP_2_106") (pintype "passive"))
      (node (ref "U1") (pin "107") (pinfunction "VSS_107") (pintype "passive"))
      (node (ref "U1") (pin "108") (pinfunction "VDD_108") (pintype "passive"))
      (node (ref "U1") (pin "109") (pinfunction "PA14_109") (pintype "passive"))
      (node (ref "U1") (pin "11") (pinfunction "PF1_11") (pintype "passive"))
      (node (ref "U1") (pin "110") (pinfunction "PA15_110") (pintype "passive"))
      (node (ref "U1") (pin "111") (pinfunction "PC10_111") (pintype "passive"))
      (node (ref "U1") (pin "112") (pinfunction "PC11_112") (pintype "passive"))
      (node (ref "U1") (pin "113") (pinfunction "PC12_113") (pintype "passive"))
      (node (ref "U1") (pin "114") (pinfunction "PD0_114") (pintype "passive"))
      (node (ref "U1") (pin "115") (pinfunction "PD1_115") (pintype "passive"))
      (node (ref "U1") (pin "116") (pinfunction "PD2_116") (pintype "passive"))
      (node (ref "U1") (pin "117") (pinfunction "PD3_117") (pintype "passive"))
      (node (ref "U1") (pin "118") (pinfunction "PD4_118") (pintype "passive"))
      (node (ref "U1") (pin "119") (pinfunction "PD5_119") (pintype "passive"))
      (node (ref "U1") (pin "12") (pinfunction "PF2_12") (pintype "passive"))
      (node (ref "U1") (pin "120") (pinfunction "VSS_120") (pintype "passive"))
      (node (ref "U1") (pin "121") (pinfunction "VDD_121") (pintype "passive"))
      (node (ref "U1") (pin "122") (pinfunction "PD6_122") (pintype "passive"))
      (node (ref "U1") (pin "123") (pinfunction "PD7_123") (pintype "passive"))
      (node (ref "U1") (pin "124") (pinfunction "PG9_124") (pintype "passive"))
      (node (ref "U1") (pin "125") (pinfunction "PG10_125") (pintype "passive"))
      (node (ref "U1") (pin "126") (pinfunction "PG11_126") (pintype "passive"))
      (node (ref "U1") (pin "127") (pinfunction "PG12_127") (pintype "passive"))
      (node (ref "U1") (pin "128") (pinfunction "PG13_128") (pintype "passive"))
      (node (ref "U1") (pin "129") (pinfunction "PG14_129") (pintype "passive"))
      (node (ref "U1") (pin "13") (pinfunction "PF3_13") (pintype "passive"))
      (node (ref "U1") (pin "130") (pinfunction "VSS_130") (pintype "passive"))
      (node (ref "U1") (pin "131") (pinfunction "VDD_131") (pintype "passive"))
      (node (ref "U1") (pin "132") (pinfunction "PG15_132") (pintype "passive"))
      (node (ref "U1") (pin "134") (pinfunction "PB4_134") (pintype "passive"))
      (node (ref "U1") (pin "135") (pinfunction "PB5_135") (pintype "passive"))
      (node (ref "U1") (pin "136") (pinfunction "PB6_136") (pintype "passive"))
      (node (ref "U1") (pin "137") (pinfunction "PB7_137") (pintype "passive"))
      (node (ref "U1") (pin "138") (pinfunction "BOOT0_138") (pintype "passive"))
      (node (ref "U1") (pin "139") (pinfunction "PB8_139") (pintype "passive"))
      (node (ref "U1") (pin "14") (pinfunction "PF4_14") (pintype "passive"))
      (node (ref "U1") (pin "140") (pinfunction "PB9_140") (pintype "passive"))
      (node (ref "U1") (pin "142") (pinfunction "PE1_142") (pintype "passive"))
      (node (ref "U1") (pin "143") (pinfunction "PDR_ON_143") (pintype "passive"))
      (node (ref "U1") (pin "144") (pinfunction "VDD_144") (pintype "passive"))
      (node (ref "U1") (pin "15") (pinfunction "PF5_15") (pintype "passive"))
      (node (ref "U1") (pin "16") (pinfunction "VSS_16") (pintype "passive"))
      (node (ref "U1") (pin "17") (pinfunction "VDD_17") (pintype "passive"))
      (node (ref "U1") (pin "18") (pinfunction "PF6_18") (pintype "passive"))
      (node (ref "U1") (pin "19") (pinfunction "PF7_19") (pintype "passive"))
      (node (ref "U1") (pin "2") (pinfunction "PE3_2") (pintype "passive"))
      (node (ref "U1") (pin "20") (pinfunction "PF8_20") (pintype "passive"))
      (node (ref "U1") (pin "21") (pinfunction "PF9_21") (pintype "passive"))
      (node (ref "U1") (pin "22") (pinfunction "PF10_22") (pintype "passive"))
      (node (ref "U1") (pin "23") (pinfunction "PH0_23") (pintype "passive"))
      (node (ref "U1") (pin "24") (pinfunction "PH1_24") (pintype "passive"))
      (node (ref "U1") (pin "25") (pinfunction "NRST_25") (pintype "passive"))
      (node (ref "U1") (pin "26") (pinfunction "PC0_26") (pintype "passive"))
      (node (ref "U1") (pin "27") (pinfunction "PC1_27") (pintype "passive"))
      (node (ref "U1") (pin "28") (pinfunction "PC2_28") (pintype "passive"))
      (node (ref "U1") (pin "29") (pinfunction "PC3_29") (pintype "passive"))
      (node (ref "U1") (pin "3") (pinfunction "PE4_3") (pintype "passive"))
      (node (ref "U1") (pin "30") (pinfunction "VDD_30") (pintype "passive"))
      (node (ref "U1") (pin "32") (pinfunction "VREF+_32") (pintype "passive"))
      (node (ref "U1") (pin "33") (pinfunction "VDDA_33") (pintype "passive"))
      (node (ref "U1") (pin "34") (pinfunction "PA0_34") (pintype "passive"))
      (node (ref "U1") (pin "35") (pinfunction "PA1_35") (pintype "passive"))
      (node (ref "U1") (pin "36") (pinfunction "PA2_36") (pintype "passive"))
      (node (ref "U1") (pin "37") (pinfunction "PA3_37") (pintype "passive"))
      (node (ref "U1") (pin "38") (pinfunction "VSS_38") (pintype "passive"))
      (node (ref "U1") (pin "39") (pinfunction "VDD_39") (pintype "passive"))
      (node (ref "U1") (pin "4") (pinfunction "PE5_4") (pintype "passive"))
      (node (ref "U1") (pin "40") (pinfunction "PA4_40") (pintype "passive"))
      (node (ref "U1") (pin "41") (pinfunction "PA5_41") (pintype "passive"))
      (node (ref "U1") (pin "42") (pinfunction "PA6_42") (pintype "passive"))
      (node (ref "U1") (pin "43") (pinfunction "PA7_43") (pintype "passive"))
      (node (ref "U1") (pin "44") (pinfunction "PC4_44") (pintype "passive"))
      (node (ref "U1") (pin "45") (pinfunction "PC5_45") (pintype "passive"))
      (node (ref "U1") (pin "46") (pinfunction "PB0_46") (pintype "passive"))
      (node (ref "U1") (pin "47") (pinfunction "PB1_47") (pintype "passive"))
      (node (ref "U1") (pin "48") (pinfunction "PB2_48") (pintype "passive"))
      (node (ref "U1") (pin "49") (pinfunction "PF11_49") (pintype "passive"))
      (node (ref "U1") (pin "5") (pinfunction "PE6_5") (pintype "passive"))
      (node (ref "U1") (pin "50") (pinfunction "PF12_50") (pintype "passive"))
      (node (ref "U1") (pin "51") (pinfunction "VSS_51") (pintype "passive"))
      (node (ref "U1") (pin "52") (pinfunction "VDD_52") (pintype "passive"))
      (node (ref "U1") (pin "53") (pinfunction "PF13_53") (pintype "passive"))
      (node (ref "U1") (pin "54") (pinfunction "PF14_54") (pintype "passive"))
      (node (ref "U1") (pin "55") (pinfunction "PF15_55") (pintype "passive"))
      (node (ref "U1") (pin "56") (pinfunction "PG0_56") (pintype "passive"))
      (node (ref "U1") (pin "57") (pinfunction "PG1_57") (pintype "passive"))
      (node (ref "U1") (pin "58") (pinfunction "PE7_58") (pintype "passive"))
      (node (ref "U1") (pin "59") (pinfunction "PE8_59") (pintype "passive"))
      (node (ref "U1") (pin "6") (pinfunction "VBAT_6") (pintype "passive"))
      (node (ref "U1") (pin "60") (pinfunction "PE9_60") (pintype "passive"))
      (node (ref "U1") (pin "61") (pinfunction "VSS_61") (pintype "passive"))
      (node (ref "U1") (pin "62") (pinfunction "VDD_62") (pintype "passive"))
      (node (ref "U1") (pin "63") (pinfunction "PE10_63") (pintype "passive"))
      (node (ref "U1") (pin "64") (pinfunction "PE11_64") (pintype "passive"))
      (node (ref "U1") (pin "65") (pinfunction "PE12_65") (pintype "passive"))
      (node (ref "U1") (pin "66") (pinfunction "PE13_66") (pintype "passive"))
      (node (ref "U1") (pin "67") (pinfunction "PE14_67") (pintype "passive"))
      (node (ref "U1") (pin "68") (pinfunction "PE15_68") (pintype "passive"))
      (node (ref "U1") (pin "69") (pinfunction "PB10_69") (pintype "passive"))
      (node (ref "U1") (pin "7") (pinfunction "PC13_7") (pintype "passive"))
      (node (ref "U1") (pin "70") (pinfunction "PB11_70") (pintype "passive"))
      (node (ref "U1") (pin "71") (pinfunction "VCAP_1_71") (pintype "passive"))
      (node (ref "U1") (pin "72") (pinfunction "VDD_72") (pintype "passive"))
      (node (ref "U1") (pin "73") (pinfunction "PB12_73") (pintype "passive"))
      (node (ref "U1") (pin "74") (pinfunction "PB13_74") (pintype "passive"))
      (node (ref "U1") (pin "75") (pinfunction "PB14_75") (pintype "passive"))
      (node (ref "U1") (pin "76") (pinfunction "PB15_76") (pintype "passive"))
      (node (ref "U1") (pin "77") (pinfunction "PD8_77") (pintype "passive"))
      (node (ref "U1") (pin "78") (pinfunction "PD9_78") (pintype "passive"))
      (node (ref "U1") (pin "79") (pinfunction "PD10_79") (pintype "passive"))
      (node (ref "U1") (pin "8") (pinfunction "PC14_8") (pintype "passive"))
      (node (ref "U1") (pin "80") (pinfunction "PD11_80") (pintype "passive"))
      (node (ref "U1") (pin "81") (pinfunction "PD12_81") (pintype "passive"))
      (node (ref "U1") (pin "82") (pinfunction "PD13_82") (pintype "passive"))
      (node (ref "U1") (pin "83") (pinfunction "VSS_83") (pintype "passive"))
      (node (ref "U1") (pin "84") (pinfunction "VDD_84") (pintype "passive"))
      (node (ref "U1") (pin "85") (pinfunction "PD14_85") (pintype "passive"))
      (node (ref "U1") (pin "86") (pinfunction "PD15_86") (pintype "passive"))
      (node (ref "U1") (pin "87") (pinfunction "PG2_87") (pintype "passive"))
      (node (ref "U1") (pin "88") (pinfunction "PG3_88") (pintype "passive"))
      (node (ref "U1") (pin "89") (pinfunction "PG4_89") (pintype "passive"))
      (node (ref "U1") (pin "9") (pinfunction "PC15_9") (pintype "passive"))
      (node (ref "U1") (pin "90") (pinfunction "PG5_90") (pintype "passive"))
      (node (ref "U1") (pin "91") (pinfunction "PG6_91") (pintype "passive"))
      (node (ref "U1") (pin "92") (pinfunction "PG7_92") (pintype "passive"))
      (node (ref "U1") (pin "93") (pinfunction "PG8_93") (pintype "passive"))
      (node (ref "U1") (pin "94") (pinfunction "VSS_94") (pintype "passive"))
      (node (ref "U1") (pin "95") (pinfunction "VDD_95") (pintype "passive"))
      (node (ref "U1") (pin "96") (pinfunction "PC6_96") (pintype "passive"))
      (node (ref "U1") (pin "97") (pinfunction "PC7_97") (pintype "passive"))
      (node (ref "U1") (pin "98") (pinfunction "PC8_98") (pintype "passive"))
      (node (ref "U1") (pin "99") (pinfunction "PC9_99") (pintype "passive"))
      (node (ref "U2") (pin "1") (pinfunction "A4_1") (pintype "passive"))
      (node (ref "U2") (pin "10") (pinfunction "I/O3_10") (pintype "passive"))
      (node (ref "U2") (pin "11") (pinfunction "VDD_11") (pintype "passive"))
      (node (ref "U2") (pin "13") (pinfunction "I/O4_13") (pintype "passive"))
      (node (ref "U2") (pin "14") (pinfunction "I/O5_14") (pintype "passive"))
      (node (ref "U2") (pin "15") (pinfunction "I/O6_15") (pintype "passive"))
      (node (ref "U2") (pin "16") (pinfunction "I/O7_16") (pintype "passive"))
      (node (ref "U2") (pin "17") (pinfunction "WE#_17") (pintype "passive"))
      (node (ref "U2") (pin "18") (pinfunction "A16_18") (pintype "passive"))
      (node (ref "U2") (pin "19") (pinfunction "A15_19") (pintype "passive"))
      (node (ref "U2") (pin "2") (pinfunction "A3_2") (pintype "passive"))
      (node (ref "U2") (pin "20") (pinfunction "A14_20") (pintype "passive"))
      (node (ref "U2") (pin "21") (pinfunction "A13_21") (pintype "passive"))
      (node (ref "U2") (pin "22") (pinfunction "A12_22") (pintype "passive"))
      (node (ref "U2") (pin "23") (pinfunction "A17_23") (pintype "passive"))
      (node (ref "U2") (pin "24") (pinfunction "A11_24") (pintype "passive"))
      (node (ref "U2") (pin "25") (pinfunction "A10_25") (pintype "passive"))
      (node (ref "U2") (pin "26") (pinfunction "A9_26") (pintype "passive"))
      (node (ref "U2") (pin "27") (pinfunction "A8_27") (pintype "passive"))
      (node (ref "U2") (pin "28") (pinfunction "A18_28") (pintype "passive"))
      (node (ref "U2") (pin "29") (pinfunction "I/O8_29") (pintype "passive"))
      (node (ref "U2") (pin "3") (pinfunction "A2_3") (pintype "passive"))
      (node (ref "U2") (pin "30") (pinfunction "I/O9_30") (pintype "passive"))
      (node (ref "U2") (pin "31") (pinfunction "I/O10_31") (pintype "passive"))
      (node (ref "U2") (pin "32") (pinfunction "I/O11_32") (pintype "passive"))
      (node (ref "U2") (pin "33") (pinfunction "VDD_33") (pintype "passive"))
      (node (ref "U2") (pin "35") (pinfunction "I/O12_35") (pintype "passive"))
      (node (ref "U2") (pin "36") (pinfunction "I/O13_36") (pintype "passive"))
      (node (ref "U2") (pin "37") (pinfunction "I/O14_37") (pintype "passive"))
      (node (ref "U2") (pin "38") (pinfunction "I/O15_38") (pintype "passive"))
      (node (ref "U2") (pin "4") (pinfunction "A1_4") (pintype "passive"))
      (node (ref "U2") (pin "40") (pinfunction "UB#_40") (pintype "passive"))
      (node (ref "U2") (pin "41") (pinfunction "OE#_41") (pintype "passive"))
      (node (ref "U2") (pin "42") (pinfunction "A7_42") (pintype "passive"))
      (node (ref "U2") (pin "43") (pinfunction "A6_43") (pintype "passive"))
      (node (ref "U2") (pin "44") (pinfunction "A5_44") (pintype "passive"))
      (node (ref "U2") (pin "5") (pinfunction "A0_5") (pintype "passive"))
      (node (ref "U2") (pin "6") (pinfunction "CS1#_6") (pintype "passive"))
      (node (ref "U2") (pin "7") (pinfunction "I/O0_7") (pintype "passive"))
      (node (ref "U2") (pin "8") (pinfunction "I/O1_8") (pintype "passive"))
      (node (ref "U2") (pin "9") (pinfunction "I/O2_9") (pintype "passive"))
      (node (ref "U3") (pin "1") (pinfunction "CS#_1") (pintype "passive"))
      (node (ref "U3") (pin "2") (pinfunction "DO_2") (pintype "passive"))
      (node (ref "U3") (pin "3") (pinfunction "IO2_3") (pintype "passive"))
      (node (ref "U3") (pin "5") (pinfunction "DI_5") (pintype "passive"))
      (node (ref "U3") (pin "7") (pinfunction "IO3_7") (pintype "passive"))
      (node (ref "U3") (pin "8") (pinfunction "VCC_8") (pintype "passive"))
      (node (ref "Y1") (pin "1") (pinfunction "OSC1_1") (pintype "passive"))
      (node (ref "Y1") (pin "2") (pinfunction "OSC2_2") (pintype "passive"))
      (node (ref "Y2") (pin "1") (pinfunction "OSC1_1") (pintype "passive"))
      (node (ref "Y2") (pin "2") (pinfunction "OSC2_2") (pintype "passive"))
    )
    (net (code "4") (name "GND") (class "Default")
      (node (ref "C1") (pin "1") (pinfunction "1_1") (pintype "passive"))
      (node (ref "C10") (pin "1") (pinfunction "1_1") (pintype "passive"))
      (node (ref "C11") (pin "1") (pinfunction "1_1") (pintype "passive"))
      (node (ref "C12") (pin "1") (pinfunction "1_1") (pintype "passive"))
      (node (ref "C13") (pin "1") (pinfunction "1_1") (pintype "passive"))
      (node (ref "C14") (pin "1") (pinfunction "1_1") (pintype "passive"))
      (node (ref "C15") (pin "1") (pinfunction "1_1") (pintype "passive"))
      (node (ref "C16") (pin "1") (pinfunction "1_1") (pintype "passive"))
      (node (ref "C17") (pin "1") (pinfunction "1_1") (pintype "passive"))
      (node (ref "C18") (pin "1") (pinfunction "1_1") (pintype "passive"))
      (node (ref "C19") (pin "1") (pinfunction "1_1") (pintype "passive"))
      (node (ref "C2") (pin "1") (pinfunction "1_1") (pintype "passive"))
      (node (ref "C20") (pin "1") (pinfunction "1_1") (pintype "passive"))
      (node (ref "C21") (pin "1") (pinfunction "1_1") (pintype "passive"))
      (node (ref "C22") (pin "1") (pinfunction "1_1") (pintype "passive"))
      (node (ref "C23") (pin "1") (pinfunction "1_1") (pintype "passive"))
      (node (ref "C24") (pin "1") (pinfunction "1_1") (pintype "passive"))
      (node (ref "C25") (pin "1") (pinfunction "1_1") (pintype "passive"))
      (node (ref "C26") (pin "1") (pinfunction "1_1") (pintype "passive"))
      (node (ref "C3") (pin "1") (pinfunction "1_1") (pintype "passive"))
      (node (ref "C4") (pin "1") (pinfunction "1_1") (pintype "passive"))
      (node (ref "C5") (pin "2") (pinfunction "2_2") (pintype "passive"))
      (node (ref "C6") (pin "2") (pinfunction "2_2") (pintype "passive"))
      (node (ref "C7") (pin "1") (pinfunction "1_1") (pintype "passive"))
      (node (ref "C8") (pin "2") (pinfunction "2_2") (pintype "passive"))
      (node (ref "C86") (pin "2") (pinfunction "2_2") (pintype "passive"))
      (node (ref "C87") (pin "2") (pinfunction "2_2") (pintype "passive"))
      (node (ref "C9") (pin "2") (pinfunction "2_2") (pintype "passive"))
      (node (ref "H1") (pin "55") (pinfunction "55_55") (pintype "passive"))
      (node (ref "H2") (pin "55") (pinfunction "55_55") (pintype "passive"))
      (node (ref "KEY1") (pin "2") (pinfunction "2_2") (pintype "passive"))
      (node (ref "R1") (pin "2") (pinfunction "2_2") (pintype "passive"))
      (node (ref "R2") (pin "2") (pinfunction "2_2") (pintype "passive"))
      (node (ref "R3") (pin "2") (pinfunction "2_2") (pintype "passive"))
      (node (ref "U1") (pin "31") (pinfunction "VSSA_31") (pintype "passive"))
      (node (ref "U2") (pin "12") (pinfunction "GND_12") (pintype "passive"))
      (node (ref "U2") (pin "34") (pinfunction "GND_34") (pintype "passive"))
      (node (ref "U3") (pin "4") (pinfunction "GND_4") (pintype "passive"))
    )
  )
)
